# SOT23-6-normal.net
KiCad netlist of a schematic drawn in EAGLE
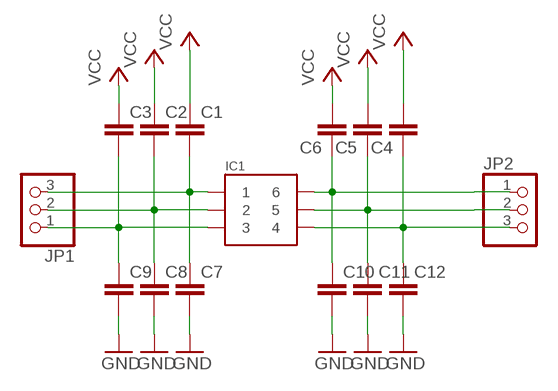
[diagram p0: schematic, sheet 1]

(export (version "E")
  (design (tool "Eeschema 10.0.6"))
  (components
    (comp (ref "C1")
      (value "C-EUC0805")
      (footprint "eagle-import:C0805")
      (libsource (lib "eagle-import") (part "C-EUC0805"))
    )
    (comp (ref "C2")
      (value "C-EUC0805")
      (footprint "eagle-import:C0805")
      (libsource (lib "eagle-import") (part "C-EUC0805"))
    )
    (comp (ref "C3")
      (value "C-EUC0805")
      (footprint "eagle-import:C0805")
      (libsource (lib "eagle-import") (part "C-EUC0805"))
    )
    (comp (ref "C4")
      (value "C-EUC0805")
      (footprint "eagle-import:C0805")
      (libsource (lib "eagle-import") (part "C-EUC0805"))
    )
    (comp (ref "C5")
      (value "C-EUC0805")
      (footprint "eagle-import:C0805")
      (libsource (lib "eagle-import") (part "C-EUC0805"))
    )
    (comp (ref "C6")
      (value "C-EUC0805")
      (footprint "eagle-import:C0805")
      (libsource (lib "eagle-import") (part "C-EUC0805"))
    )
    (comp (ref "C7")
      (value "C-EUC0603")
      (footprint "eagle-import:C0603")
      (libsource (lib "eagle-import") (part "C-EUC0603"))
    )
    (comp (ref "C8")
      (value "C-EUC0603")
      (footprint "eagle-import:C0603")
      (libsource (lib "eagle-import") (part "C-EUC0603"))
    )
    (comp (ref "C9")
      (value "C-EUC0603")
      (footprint "eagle-import:C0603")
      (libsource (lib "eagle-import") (part "C-EUC0603"))
    )
    (comp (ref "C10")
      (value "C-EUC0603")
      (footprint "eagle-import:C0603")
      (libsource (lib "eagle-import") (part "C-EUC0603"))
    )
    (comp (ref "C11")
      (value "C-EUC0603")
      (footprint "eagle-import:C0603")
      (libsource (lib "eagle-import") (part "C-EUC0603"))
    )
    (comp (ref "C12")
      (value "C-EUC0603")
      (footprint "eagle-import:C0603")
      (libsource (lib "eagle-import") (part "C-EUC0603"))
    )
    (comp (ref "IC1")
      (value "2X3-PIN-SOT23")
      (footprint "eagle-import:SOT23-6")
      (libsource (lib "eagle-import") (part "2X3-PIN-SOT23"))
    )
    (comp (ref "JP1")
      (value "PINHD-1X3")
      (footprint "eagle-import:1X03")
      (libsource (lib "eagle-import") (part "PINHD-1X3"))
    )
    (comp (ref "JP2")
      (value "PINHD-1X3")
      (footprint "eagle-import:1X03")
      (libsource (lib "eagle-import") (part "PINHD-1X3"))
    )
  )
  (nets
    (net (code "1") (name "GND") (class "Default")
      (node (ref "C10") (pin "2") (pinfunction "2_2") (pintype "passive"))
      (node (ref "C11") (pin "2") (pinfunction "2_2") (pintype "passive"))
      (node (ref "C12") (pin "2") (pinfunction "2_2") (pintype "passive"))
      (node (ref "C7") (pin "2") (pinfunction "2_2") (pintype "passive"))
      (node (ref "C8") (pin "2") (pinfunction "2_2") (pintype "passive"))
      (node (ref "C9") (pin "2") (pinfunction "2_2") (pintype "passive"))
    )
    (net (code "2") (name "Net-(IC1-1)") (class "Default")
      (node (ref "C1") (pin "2") (pinfunction "2_2") (pintype "passive"))
      (node (ref "C7") (pin "1") (pinfunction "1_1") (pintype "passive"))
      (node (ref "IC1") (pin "P$1") (pinfunction "1_P$1") (pintype "bidirectional"))
      (node (ref "JP1") (pin "3") (pinfunction "3_3") (pintype "passive"))
    )
    (net (code "3") (name "Net-(IC1-2)") (class "Default")
      (node (ref "C2") (pin "2") (pinfunction "2_2") (pintype "passive"))
      (node (ref "C8") (pin "1") (pinfunction "1_1") (pintype "passive"))
      (node (ref "IC1") (pin "P$2") (pinfunction "2_P$2") (pintype "bidirectional"))
      (node (ref "JP1") (pin "2") (pinfunction "2_2") (pintype "passive"))
    )
    (net (code "4") (name "Net-(IC1-3)") (class "Default")
      (node (ref "C3") (pin "2") (pinfunction "2_2") (pintype "passive"))
      (node (ref "C9") (pin "1") (pinfunction "1_1") (pintype "passive"))
      (node (ref "IC1") (pin "P$3") (pinfunction "3_P$3") (pintype "bidirectional"))
      (node (ref "JP1") (pin "1") (pinfunction "1_1") (pintype "passive"))
    )
    (net (code "5") (name "Net-(IC1-4)") (class "Default")
      (node (ref "C12") (pin "1") (pinfunction "1_1") (pintype "passive"))
      (node (ref "C4") (pin "1") (pinfunction "1_1") (pintype "passive"))
      (node (ref "IC1") (pin "P$4") (pinfunction "4_P$4") (pintype "bidirectional"))
      (node (ref "JP2") (pin "3") (pinfunction "3_3") (pintype "passive"))
    )
    (net (code "6") (name "Net-(IC1-5)") (class "Default")
      (node (ref "C11") (pin "1") (pinfunction "1_1") (pintype "passive"))
      (node (ref "C5") (pin "1") (pinfunction "1_1") (pintype "passive"))
      (node (ref "IC1") (pin "P$5") (pinfunction "5_P$5") (pintype "bidirectional"))
      (node (ref "JP2") (pin "2") (pinfunction "2_2") (pintype "passive"))
    )
    (net (code "7") (name "Net-(IC1-6)") (class "Default")
      (node (ref "C10") (pin "1") (pinfunction "1_1") (pintype "passive"))
      (node (ref "C6") (pin "1") (pinfunction "1_1") (pintype "passive"))
      (node (ref "IC1") (pin "P$6") (pinfunction "6_P$6") (pintype "bidirectional"))
      (node (ref "JP2") (pin "1") (pinfunction "1_1") (pintype "passive"))
    )
    (net (code "8") (name "VCC") (class "Default")
      (node (ref "C1") (pin "1") (pinfunction "1_1") (pintype "passive"))
      (node (ref "C2") (pin "1") (pinfunction "1_1") (pintype "passive"))
      (node (ref "C3") (pin "1") (pinfunction "1_1") (pintype "passive"))
      (node (ref "C4") (pin "2") (pinfunction "2_2") (pintype "passive"))
      (node (ref "C5") (pin "2") (pinfunction "2_2") (pintype "passive"))
      (node (ref "C6") (pin "2") (pinfunction "2_2") (pintype "passive"))
    )
  )
)
